# No_Inversor.net
KiCad netlist of a schematic drawn in Altium Designer
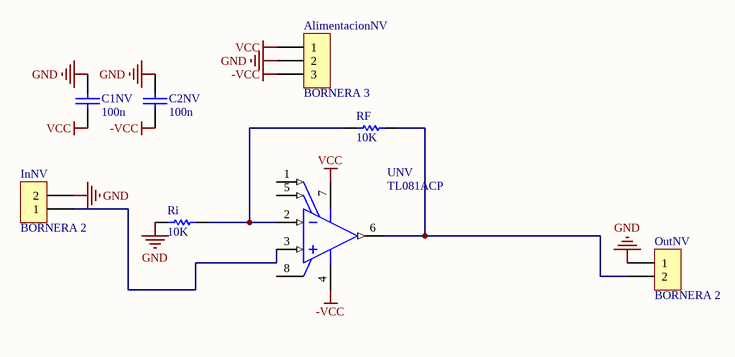
[diagram p0: No_Inversor.SchDoc]

(export (version "E")
  (design (tool "Eeschema 10.0.6"))
  (components
    (comp (ref "AlimentacionNV")
      (value "BORNERA 3")
      (footprint "BORNERA3")
      (libsource (lib "LIB PIO IX") (part "BORNERA 3"))
    )
    (comp (ref "C1NV") (value "100n") (footprint "0805") (libsource (lib "LIB PIO IX") (part "CAP")))
    (comp (ref "C2NV") (value "100n") (footprint "0805") (libsource (lib "LIB PIO IX") (part "CAP")))
    (comp (ref "InNV")
      (value "BORNERA 2")
      (footprint "BORNERA2")
      (libsource (lib "LIB PIO IX") (part "BORNERA 2"))
    )
    (comp (ref "OutNV") (value "BORNERA 2") (footprint "BORNERA2") (libsource (lib "") (part "BORNERA 2_1")))
    (comp (ref "RF") (value "10K") (footprint "0805") (libsource (lib "LIB PIO IX") (part "RES")))
    (comp (ref "Ri") (value "10K") (footprint "0805") (libsource (lib "LIB PIO IX") (part "RES")))
    (comp (ref "UNV")
      (value "TL081ACP")
      (footprint "TI-P8")
      (description "JFET-Input Operational Amplifier, 7 to 36 V, 0 to 70 degC, 8-pin DIP (P8), Pb-Free (RoHS)")
      (fields (field (name "MANUFACTURER") "Texas Instruments"))
      (libsource (lib "TI Amplifiers and Linear Operational Amplifier General Purpose") (part "TL081ACP"))
    )
  )
  (nets
    (net (code "1") (name "-VCC") (class "Default")
      (node (ref "AlimentacionNV") (pin "3") (pinfunction "3_3") (pintype "passive"))
      (node (ref "C2NV") (pin "2") (pinfunction "2_2") (pintype "passive"))
      (node (ref "UNV") (pin "4") (pinfunction "VCC-_4") (pintype "power_in"))
    )
    (net (code "2") (name "GND") (class "Default")
      (node (ref "AlimentacionNV") (pin "2") (pinfunction "2_2") (pintype "passive"))
      (node (ref "C1NV") (pin "1") (pinfunction "1_1") (pintype "passive"))
      (node (ref "C2NV") (pin "1") (pinfunction "1_1") (pintype "passive"))
      (node (ref "InNV") (pin "2") (pinfunction "2_2") (pintype "passive"))
      (node (ref "OutNV") (pin "1") (pinfunction "1_1") (pintype "passive"))
      (node (ref "Ri") (pin "1") (pinfunction "1_1") (pintype "passive"))
    )
    (net (code "3") (name "Net-(UNV-IN+)") (class "Default")
      (node (ref "InNV") (pin "1") (pinfunction "1_1") (pintype "passive"))
      (node (ref "UNV") (pin "3") (pinfunction "IN+_3") (pintype "input"))
    )
    (net (code "4") (name "Net-(UNV-IN-)") (class "Default")
      (node (ref "RF") (pin "1") (pinfunction "1_1") (pintype "passive"))
      (node (ref "Ri") (pin "2") (pinfunction "2_2") (pintype "passive"))
      (node (ref "UNV") (pin "2") (pinfunction "IN-_2") (pintype "input"))
    )
    (net (code "5") (name "Net-(UNV-OUT)") (class "Default")
      (node (ref "OutNV") (pin "2") (pinfunction "2_2") (pintype "passive"))
      (node (ref "RF") (pin "2") (pinfunction "2_2") (pintype "passive"))
      (node (ref "UNV") (pin "6") (pinfunction "OUT_6") (pintype "output"))
    )
    (net (code "6") (name "VCC") (class "Default")
      (node (ref "AlimentacionNV") (pin "1") (pinfunction "1_1") (pintype "passive"))
      (node (ref "C1NV") (pin "2") (pinfunction "2_2") (pintype "passive"))
      (node (ref "UNV") (pin "7") (pinfunction "VCC+_7") (pintype "power_in"))
    )
    (net (code "7") (name "unconnected-(UNV-NC-Pad8)") (class "Default")
      (node (ref "UNV") (pin "8") (pinfunction "NC_8") (pintype "passive"))
    )
    (net (code "8") (name "unconnected-(UNV-OFFSET_N1-Pad1)") (class "Default")
      (node (ref "UNV") (pin "1") (pinfunction "OFFSET_N1_1") (pintype "input"))
    )
    (net (code "9") (name "unconnected-(UNV-OFFSET_N2-Pad5)") (class "Default")
      (node (ref "UNV") (pin "5") (pinfunction "OFFSET_N2_5") (pintype "input"))
    )
  )
)
